# glass_udrive_pcb.net
KiCad netlist of a schematic drawn in EAGLE
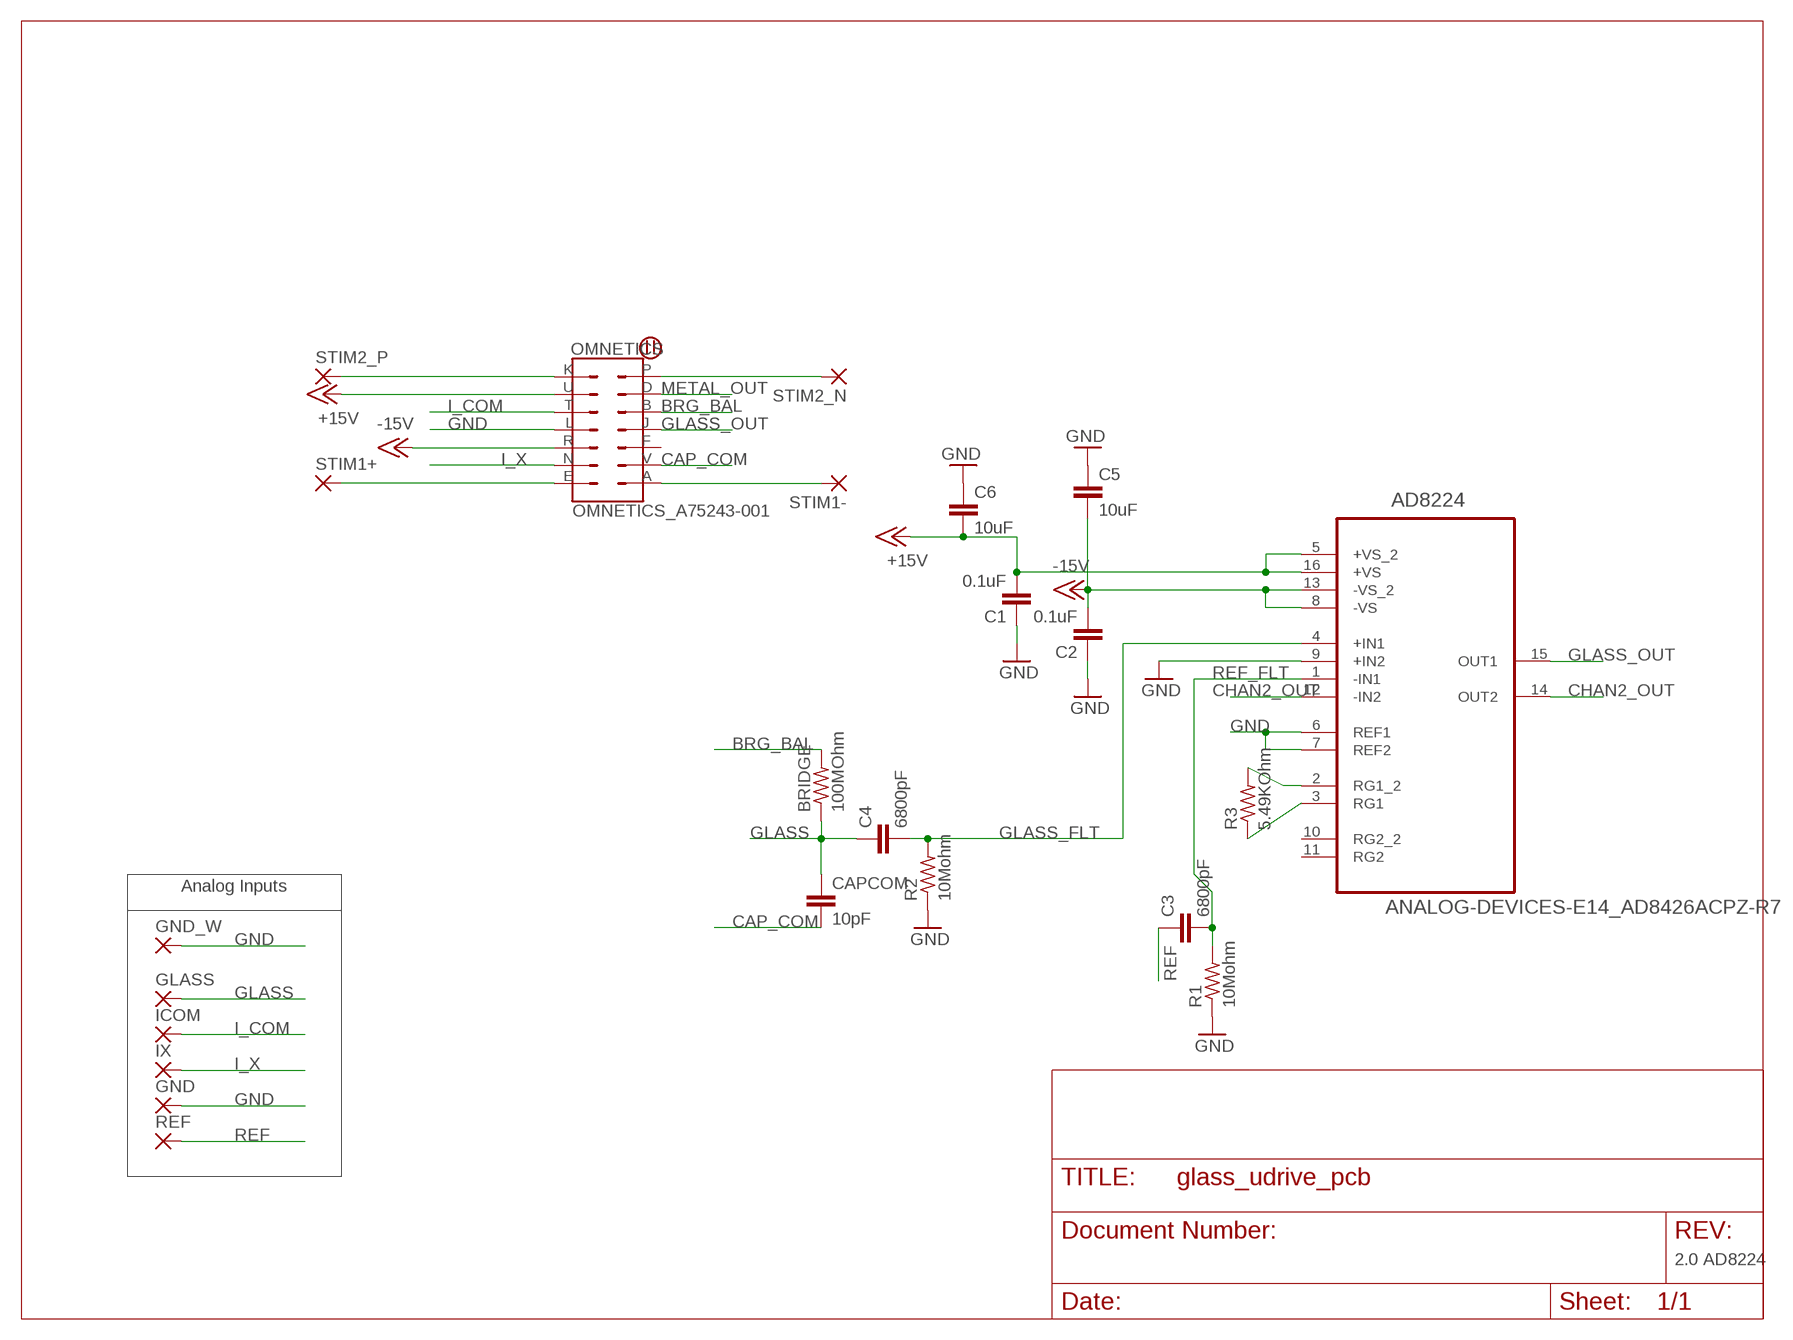
[diagram p0: schematic, sheet 1]

(export (version "E")
  (design (tool "Eeschema 10.0.6"))
  (components
    (comp (ref "AD8224")
      (value "ANALOG-DEVICES-E14_AD8426ACPZ-R7")
      (footprint "eagle-import:ANALOG-DEVICES-E14_QFN65P400X400X100-16N")
      (fields (field (name "MPN") "AD8426ACPZ-R7"))
      (libsource (lib "eagle-import") (part "ANALOG-DEVICES-E14_AD8426ACPZ-R7"))
    )
    (comp (ref "BRIDGE")
      (value "100MOhm")
      (footprint "eagle-import:1206")
      (libsource (lib "eagle-import") (part "R_1206"))
    )
    (comp (ref "C1")
      (value "0.1uF")
      (footprint "eagle-import:0201")
      (libsource (lib "eagle-import") (part "C_0201"))
    )
    (comp (ref "C2")
      (value "0.1uF")
      (footprint "eagle-import:0201")
      (libsource (lib "eagle-import") (part "C_0201"))
    )
    (comp (ref "C3")
      (value "6800pF")
      (footprint "eagle-import:0201")
      (libsource (lib "eagle-import") (part "C_0201"))
    )
    (comp (ref "C4")
      (value "6800pF")
      (footprint "eagle-import:0201")
      (libsource (lib "eagle-import") (part "C_0201"))
    )
    (comp (ref "C5")
      (value "10uF")
      (footprint "eagle-import:0603")
      (libsource (lib "eagle-import") (part "C_0603"))
    )
    (comp (ref "C6")
      (value "10uF")
      (footprint "eagle-import:0603")
      (libsource (lib "eagle-import") (part "C_0603"))
    )
    (comp (ref "CAPCOM")
      (value "10pF")
      (footprint "eagle-import:0402")
      (libsource (lib "eagle-import") (part "C_0402"))
    )
    (comp (ref "GLASS")
      (value "THROUGH-HOLE-30MIL/15MIL")
      (footprint "eagle-import:30MIL_15MIL")
      (libsource (lib "eagle-import") (part "THROUGH-HOLE-30MIL/15MIL"))
    )
    (comp (ref "GND")
      (value "THROUGH-HOLE-30MIL/15MIL")
      (footprint "eagle-import:30MIL_15MIL")
      (libsource (lib "eagle-import") (part "THROUGH-HOLE-30MIL/15MIL"))
    )
    (comp (ref "GND_W")
      (value "THROUGH-HOLE-30MIL/15MIL")
      (footprint "eagle-import:30MIL_15MIL")
      (libsource (lib "eagle-import") (part "THROUGH-HOLE-30MIL/15MIL"))
    )
    (comp (ref "ICOM")
      (value "THROUGH-HOLE-30MIL/15MIL")
      (footprint "eagle-import:30MIL_15MIL")
      (libsource (lib "eagle-import") (part "THROUGH-HOLE-30MIL/15MIL"))
    )
    (comp (ref "IX")
      (value "THROUGH-HOLE-30MIL/15MIL")
      (footprint "eagle-import:30MIL_15MIL")
      (libsource (lib "eagle-import") (part "THROUGH-HOLE-30MIL/15MIL"))
    )
    (comp (ref "OMNETICS")
      (value "OMNETICS_A75243-001")
      (footprint "eagle-import:OMNETICS_A75243-001")
      (libsource (lib "eagle-import") (part "OMNETICS_A75243-001"))
    )
    (comp (ref "R1")
      (value "10Mohm")
      (footprint "eagle-import:0201")
      (libsource (lib "eagle-import") (part "R_0201"))
    )
    (comp (ref "R2")
      (value "10Mohm")
      (footprint "eagle-import:0201")
      (libsource (lib "eagle-import") (part "R_0201"))
    )
    (comp (ref "R3")
      (value "5.49KOhm")
      (footprint "eagle-import:0201")
      (libsource (lib "eagle-import") (part "R_0201"))
    )
    (comp (ref "REF")
      (value "THROUGH-HOLE-30MIL/15MIL")
      (footprint "eagle-import:30MIL_15MIL")
      (libsource (lib "eagle-import") (part "THROUGH-HOLE-30MIL/15MIL"))
    )
    (comp (ref "STIM1+")
      (value "THROUGH-HOLE-30MIL/15MIL")
      (footprint "eagle-import:30MIL_15MIL")
      (libsource (lib "eagle-import") (part "THROUGH-HOLE-30MIL/15MIL"))
    )
    (comp (ref "STIM1-")
      (value "THROUGH-HOLE-30MIL/15MIL")
      (footprint "eagle-import:30MIL_15MIL")
      (libsource (lib "eagle-import") (part "THROUGH-HOLE-30MIL/15MIL"))
    )
    (comp (ref "STIM2_N")
      (value "THROUGH-HOLE-30MIL/15MIL")
      (footprint "eagle-import:30MIL_15MIL")
      (libsource (lib "eagle-import") (part "THROUGH-HOLE-30MIL/15MIL"))
    )
    (comp (ref "STIM2_P")
      (value "THROUGH-HOLE-30MIL/15MIL")
      (footprint "eagle-import:30MIL_15MIL")
      (libsource (lib "eagle-import") (part "THROUGH-HOLE-30MIL/15MIL"))
    )
  )
  (nets
    (net (code "1") (name "+15V") (class "Default")
      (node (ref "AD8224") (pin "16") (pinfunction "+VS_16") (pintype "passive"))
      (node (ref "AD8224") (pin "5") (pinfunction "+VS_2_5") (pintype "passive"))
      (node (ref "C1") (pin "2") (pinfunction "2_2") (pintype "passive"))
      (node (ref "C6") (pin "2") (pinfunction "2_2") (pintype "passive"))
      (node (ref "OMNETICS") (pin "U") (pinfunction "U_U") (pintype "passive"))
    )
    (net (code "2") (name "-15V") (class "Default")
      (node (ref "AD8224") (pin "13") (pinfunction "-VS_2_13") (pintype "passive"))
      (node (ref "AD8224") (pin "8") (pinfunction "-VS_8") (pintype "passive"))
      (node (ref "C2") (pin "2") (pinfunction "2_2") (pintype "passive"))
      (node (ref "C5") (pin "2") (pinfunction "2_2") (pintype "passive"))
      (node (ref "OMNETICS") (pin "R") (pinfunction "R_R") (pintype "passive"))
    )
    (net (code "3") (name "/BRG_BAL") (class "Default")
      (node (ref "BRIDGE") (pin "2") (pinfunction "2_2") (pintype "passive"))
      (node (ref "OMNETICS") (pin "B") (pinfunction "B_B") (pintype "passive"))
    )
    (net (code "4") (name "/CAP_COM") (class "Default")
      (node (ref "CAPCOM") (pin "2") (pinfunction "2_2") (pintype "passive"))
      (node (ref "OMNETICS") (pin "V") (pinfunction "V_V") (pintype "passive"))
    )
    (net (code "5") (name "/CHAN2_OUT") (class "Default")
      (node (ref "AD8224") (pin "12") (pinfunction "-IN2_12") (pintype "passive"))
      (node (ref "AD8224") (pin "14") (pinfunction "OUT2_14") (pintype "passive"))
    )
    (net (code "6") (name "/GLASS") (class "Default")
      (node (ref "BRIDGE") (pin "1") (pinfunction "1_1") (pintype "passive"))
      (node (ref "C4") (pin "1") (pinfunction "1_1") (pintype "passive"))
      (node (ref "CAPCOM") (pin "1") (pinfunction "1_1") (pintype "passive"))
      (node (ref "GLASS") (pin "P$1") (pinfunction "P_P$1") (pintype "passive"))
    )
    (net (code "7") (name "/GLASS_FLT") (class "Default")
      (node (ref "AD8224") (pin "4") (pinfunction "+IN1_4") (pintype "passive"))
      (node (ref "C4") (pin "2") (pinfunction "2_2") (pintype "passive"))
      (node (ref "R2") (pin "2") (pinfunction "2_2") (pintype "passive"))
    )
    (net (code "8") (name "/GLASS_OUT") (class "Default")
      (node (ref "AD8224") (pin "15") (pinfunction "OUT1_15") (pintype "passive"))
      (node (ref "OMNETICS") (pin "J") (pinfunction "J_J") (pintype "passive"))
    )
    (net (code "9") (name "/I_COM") (class "Default")
      (node (ref "ICOM") (pin "P$1") (pinfunction "P_P$1") (pintype "passive"))
      (node (ref "OMNETICS") (pin "T") (pinfunction "T_T") (pintype "passive"))
    )
    (net (code "10") (name "/I_X") (class "Default")
      (node (ref "IX") (pin "P$1") (pinfunction "P_P$1") (pintype "passive"))
      (node (ref "OMNETICS") (pin "N") (pinfunction "N_N") (pintype "passive"))
    )
    (net (code "11") (name "/METAL_OUT") (class "Default")
      (node (ref "OMNETICS") (pin "D") (pinfunction "D_D") (pintype "passive"))
    )
    (net (code "12") (name "/REF") (class "Default")
      (node (ref "C3") (pin "1") (pinfunction "1_1") (pintype "passive"))
      (node (ref "REF") (pin "P$1") (pinfunction "P_P$1") (pintype "passive"))
    )
    (net (code "13") (name "/REF_FLT") (class "Default")
      (node (ref "AD8224") (pin "1") (pinfunction "-IN1_1") (pintype "passive"))
      (node (ref "C3") (pin "2") (pinfunction "2_2") (pintype "passive"))
      (node (ref "R1") (pin "2") (pinfunction "2_2") (pintype "passive"))
    )
    (net (code "14") (name "GND") (class "Default")
      (node (ref "AD8224") (pin "6") (pinfunction "REF1_6") (pintype "passive"))
      (node (ref "AD8224") (pin "7") (pinfunction "REF2_7") (pintype "passive"))
      (node (ref "AD8224") (pin "9") (pinfunction "+IN2_9") (pintype "passive"))
      (node (ref "C1") (pin "1") (pinfunction "1_1") (pintype "passive"))
      (node (ref "C2") (pin "1") (pinfunction "1_1") (pintype "passive"))
      (node (ref "C5") (pin "1") (pinfunction "1_1") (pintype "passive"))
      (node (ref "C6") (pin "1") (pinfunction "1_1") (pintype "passive"))
      (node (ref "GND") (pin "P$1") (pinfunction "P_P$1") (pintype "passive"))
      (node (ref "GND_W") (pin "P$1") (pinfunction "P_P$1") (pintype "passive"))
      (node (ref "OMNETICS") (pin "L") (pinfunction "L_L") (pintype "passive"))
      (node (ref "R1") (pin "1") (pinfunction "1_1") (pintype "passive"))
      (node (ref "R2") (pin "1") (pinfunction "1_1") (pintype "passive"))
    )
    (net (code "15") (name "Net-(AD8224-RG1)") (class "Default")
      (node (ref "AD8224") (pin "3") (pinfunction "RG1_3") (pintype "passive"))
      (node (ref "R3") (pin "1") (pinfunction "1_1") (pintype "passive"))
    )
    (net (code "16") (name "Net-(AD8224-RG1_2)") (class "Default")
      (node (ref "AD8224") (pin "2") (pinfunction "RG1_2_2") (pintype "passive"))
      (node (ref "R3") (pin "2") (pinfunction "2_2") (pintype "passive"))
    )
    (net (code "17") (name "Net-(STIM1+-P)") (class "Default")
      (node (ref "OMNETICS") (pin "E") (pinfunction "E_E") (pintype "passive"))
      (node (ref "STIM1+") (pin "P$1") (pinfunction "P_P$1") (pintype "passive"))
    )
    (net (code "18") (name "Net-(STIM1--P)") (class "Default")
      (node (ref "OMNETICS") (pin "A") (pinfunction "A_A") (pintype "passive"))
      (node (ref "STIM1-") (pin "P$1") (pinfunction "P_P$1") (pintype "passive"))
    )
    (net (code "19") (name "Net-(STIM2_N-P)") (class "Default")
      (node (ref "OMNETICS") (pin "P") (pinfunction "P_P") (pintype "passive"))
      (node (ref "STIM2_N") (pin "P$1") (pinfunction "P_P$1") (pintype "passive"))
    )
    (net (code "20") (name "Net-(STIM2_P-P)") (class "Default")
      (node (ref "OMNETICS") (pin "K") (pinfunction "K_K") (pintype "passive"))
      (node (ref "STIM2_P") (pin "P$1") (pinfunction "P_P$1") (pintype "passive"))
    )
    (net (code "21") (name "unconnected-(AD8224-RG2-Pad11)") (class "Default")
      (node (ref "AD8224") (pin "11") (pinfunction "RG2_11") (pintype "passive"))
    )
    (net (code "22") (name "unconnected-(AD8224-RG2_2-Pad10)") (class "Default")
      (node (ref "AD8224") (pin "10") (pinfunction "RG2_2_10") (pintype "passive"))
    )
    (net (code "23") (name "unconnected-(OMNETICS-PadF)") (class "Default")
      (node (ref "OMNETICS") (pin "F") (pinfunction "F_F") (pintype "passive"))
    )
  )
)
